# SW6208_A_A_B_C_L_188.net
KiCad netlist of a schematic drawn in Altium Designer
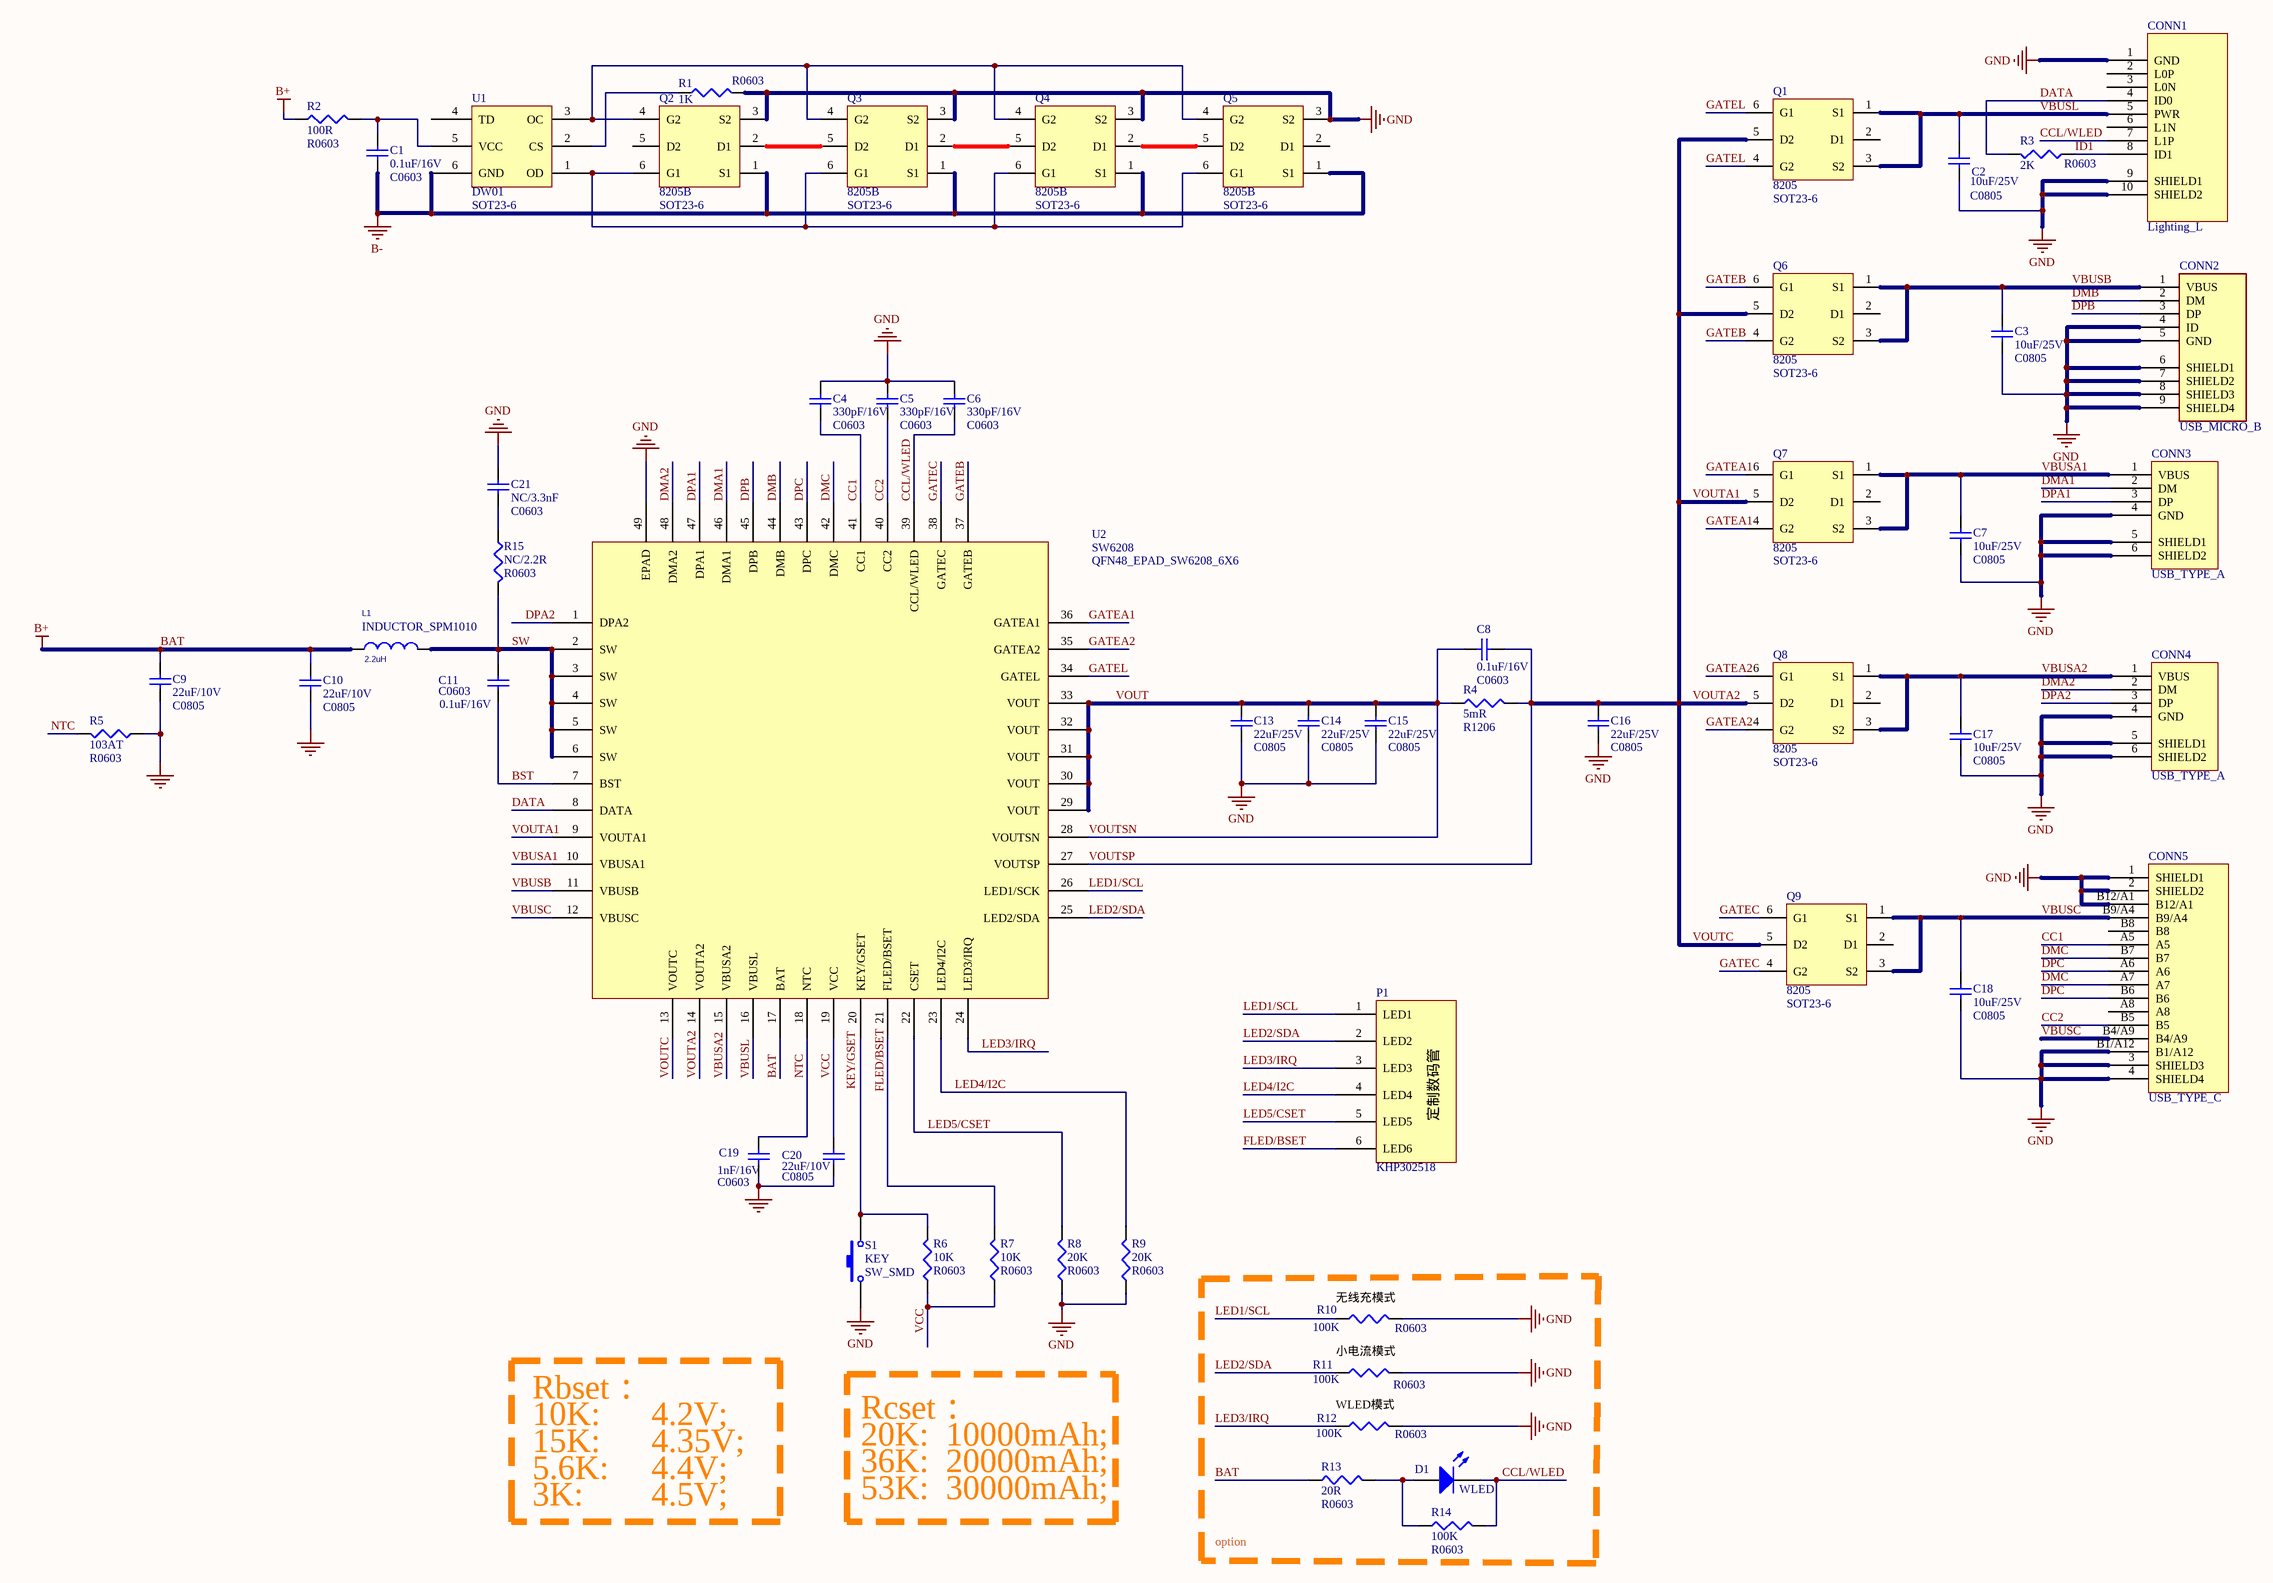
[diagram p0: SW6208+A+A+B+C+L+快充188数码管.SchDoc]

(export (version "E")
  (design (tool "Eeschema 10.0.6"))
  (components
    (comp (ref "C1")
      (value "0.1uF/16V")
      (footprint "C0603")
      (description "Capacitor")
      (fields (field (name "PUBLISHER") "Altium Limited"))
      (libsource (lib "参考设计器件原理图更新") (part "CAP0603"))
    )
    (comp (ref "C2")
      (value "10uF/25V")
      (footprint "C0805")
      (description "Capacitor")
      (fields (field (name "PUBLISHER") "Altium Limited"))
      (libsource (lib "参考设计器件原理图更新") (part "CAP0805"))
    )
    (comp (ref "C3")
      (value "10uF/25V")
      (footprint "C0805")
      (description "Capacitor")
      (fields (field (name "PUBLISHER") "Altium Limited"))
      (libsource (lib "参考设计器件原理图更新") (part "CAP0805"))
    )
    (comp (ref "C4")
      (value "330pF/16V")
      (footprint "C0603")
      (description "Capacitor")
      (fields (field (name "PUBLISHER") "Altium Limited"))
      (libsource (lib "参考设计器件原理图更新") (part "CAP0603"))
    )
    (comp (ref "C5")
      (value "330pF/16V")
      (footprint "C0603")
      (description "Capacitor")
      (fields (field (name "PUBLISHER") "Altium Limited"))
      (libsource (lib "参考设计器件原理图更新") (part "CAP0603"))
    )
    (comp (ref "C6")
      (value "330pF/16V")
      (footprint "C0603")
      (description "Capacitor")
      (fields (field (name "PUBLISHER") "Altium Limited"))
      (libsource (lib "参考设计器件原理图更新") (part "CAP0603"))
    )
    (comp (ref "C7")
      (value "10uF/25V")
      (footprint "C0805")
      (description "Capacitor")
      (fields (field (name "PUBLISHER") "Altium Limited"))
      (libsource (lib "参考设计器件原理图更新") (part "CAP0805"))
    )
    (comp (ref "C8")
      (value "0.1uF/16V")
      (footprint "C0603")
      (description "Capacitor")
      (fields (field (name "PUBLISHER") "Altium Limited"))
      (libsource (lib "参考设计器件原理图更新") (part "CAP0603"))
    )
    (comp (ref "C9")
      (value "22uF/10V")
      (footprint "C0805")
      (description "Capacitor")
      (fields (field (name "PUBLISHER") "Altium Limited"))
      (libsource (lib "参考设计器件原理图更新") (part "CAP0805"))
    )
    (comp (ref "C10")
      (value "22uF/10V")
      (footprint "C0805")
      (description "Capacitor")
      (fields (field (name "PUBLISHER") "Altium Limited"))
      (libsource (lib "参考设计器件原理图更新") (part "CAP0805"))
    )
    (comp (ref "C11")
      (value "0.1uF/16V")
      (footprint "C0603")
      (description "Capacitor")
      (fields (field (name "PUBLISHER") "Altium Limited"))
      (libsource (lib "参考设计器件原理图更新") (part "CAP0603"))
    )
    (comp (ref "C13")
      (value "22uF/25V")
      (footprint "C0805")
      (description "Capacitor")
      (fields (field (name "PUBLISHER") "Altium Limited"))
      (libsource (lib "参考设计器件原理图更新") (part "CAP0805"))
    )
    (comp (ref "C14")
      (value "22uF/25V")
      (footprint "C0805")
      (description "Capacitor")
      (fields (field (name "PUBLISHER") "Altium Limited"))
      (libsource (lib "参考设计器件原理图更新") (part "CAP0805"))
    )
    (comp (ref "C15")
      (value "22uF/25V")
      (footprint "C0805")
      (description "Capacitor")
      (fields (field (name "PUBLISHER") "Altium Limited"))
      (libsource (lib "参考设计器件原理图更新") (part "CAP0805"))
    )
    (comp (ref "C16")
      (value "22uF/25V")
      (footprint "C0805")
      (description "Capacitor")
      (fields (field (name "PUBLISHER") "Altium Limited"))
      (libsource (lib "参考设计器件原理图更新") (part "CAP0805"))
    )
    (comp (ref "C17")
      (value "10uF/25V")
      (footprint "C0805")
      (description "Capacitor")
      (fields (field (name "PUBLISHER") "Altium Limited"))
      (libsource (lib "参考设计器件原理图更新") (part "CAP0805"))
    )
    (comp (ref "C18")
      (value "10uF/25V")
      (footprint "C0805")
      (description "Capacitor")
      (fields (field (name "PUBLISHER") "Altium Limited"))
      (libsource (lib "参考设计器件原理图更新") (part "CAP0805"))
    )
    (comp (ref "C19")
      (value "1nF/16V")
      (footprint "C0603")
      (description "Capacitor")
      (fields (field (name "PUBLISHER") "Altium Limited"))
      (libsource (lib "参考设计器件原理图更新") (part "CAP0603"))
    )
    (comp (ref "C20")
      (value "22uF/10V")
      (footprint "C0805")
      (description "Capacitor")
      (fields (field (name "PUBLISHER") "Altium Limited"))
      (libsource (lib "参考设计器件原理图更新") (part "CAP0805"))
    )
    (comp (ref "C21")
      (value "NC/3.3nF")
      (footprint "C0603")
      (description "Capacitor")
      (fields (field (name "PUBLISHER") "Altium Limited"))
      (libsource (lib "参考设计器件原理图更新") (part "CAP0603"))
    )
    (comp (ref "CONN1")
      (value "Lighting_L")
      (footprint "Lighting")
      (libsource (lib "参考设计器件原理图更新") (part "LIGHTING_PORT"))
    )
    (comp (ref "CONN2")
      (value "USB_MICRO_B")
      (footprint "USB_MICRO_B")
      (libsource (lib "参考设计器件原理图更新") (part "USB_MICRO_B"))
    )
    (comp (ref "CONN3")
      (value "USB_TYPE_A")
      (footprint "USB_TYPE_A")
      (libsource (lib "参考设计器件原理图更新") (part "USB_TYPE_A"))
    )
    (comp (ref "CONN4")
      (value "USB_TYPE_A")
      (footprint "USB_TYPE_A")
      (libsource (lib "参考设计器件原理图更新") (part "USB_TYPE_A"))
    )
    (comp (ref "CONN5")
      (value "USB_TYPE_C")
      (footprint "LOUISAD:USB_TYPE_C")
      (libsource (lib "参考设计器件原理图更新") (part "USB_TYPE_C"))
    )
    (comp (ref "D1")
      (value "WLED")
      (footprint "LED_5MM")
      (fields (field (name "PUBLISHER") "Altium Limited"))
      (libsource (lib "参考设计器件原理图更新") (part "WLED"))
    )
    (comp (ref "L1")
      (value "2.2uH")
      (footprint "INDUCTOR_SPM1010")
      (description "INDUCTOR")
      (libsource (lib "参考设计器件原理图更新") (part "INDUCTOR_SPM1010"))
    )
    (comp (ref "P1")
      (value "KHP302518")
      (footprint "KHP-SEG-6")
      (libsource (lib "参考设计器件原理图更新") (part "KHP302518"))
    )
    (comp (ref "Q1")
      (value "8205")
      (footprint "SOT23-6")
      (description "NMOS")
      (fields (field (name "FOOTPRINF") "SOT23-6"))
      (libsource (lib "参考设计器件原理图更新") (part "8205"))
    )
    (comp (ref "Q2")
      (value "8205B")
      (footprint "SOT23-6")
      (description "NMOS")
      (fields (field (name "FOOTPRINF") "SOT23-6"))
      (libsource (lib "") (part "8205_1"))
    )
    (comp (ref "Q3")
      (value "8205B")
      (footprint "SOT23-6")
      (description "NMOS")
      (fields (field (name "FOOTPRINF") "SOT23-6"))
      (libsource (lib "") (part "8205_1"))
    )
    (comp (ref "Q4")
      (value "8205B")
      (footprint "SOT23-6")
      (description "NMOS")
      (fields (field (name "FOOTPRINF") "SOT23-6"))
      (libsource (lib "") (part "8205_1"))
    )
    (comp (ref "Q5")
      (value "8205B")
      (footprint "SOT23-6")
      (description "NMOS")
      (fields (field (name "FOOTPRINF") "SOT23-6"))
      (libsource (lib "") (part "8205_1"))
    )
    (comp (ref "Q6")
      (value "8205")
      (footprint "SOT23-6")
      (description "NMOS")
      (fields (field (name "FOOTPRINF") "SOT23-6"))
      (libsource (lib "参考设计器件原理图更新") (part "8205"))
    )
    (comp (ref "Q7")
      (value "8205")
      (footprint "SOT23-6")
      (description "NMOS")
      (fields (field (name "FOOTPRINF") "SOT23-6"))
      (libsource (lib "参考设计器件原理图更新") (part "8205"))
    )
    (comp (ref "Q8")
      (value "8205")
      (footprint "SOT23-6")
      (description "NMOS")
      (fields (field (name "FOOTPRINF") "SOT23-6"))
      (libsource (lib "参考设计器件原理图更新") (part "8205"))
    )
    (comp (ref "Q9")
      (value "8205")
      (footprint "SOT23-6")
      (description "NMOS")
      (fields (field (name "FOOTPRINF") "SOT23-6"))
      (libsource (lib "参考设计器件原理图更新") (part "8205"))
    )
    (comp (ref "R1")
      (value "1K")
      (footprint "R0603")
      (description "Resistor")
      (fields (field (name "PUBLISHER") "Altium Limited"))
      (libsource (lib "参考设计器件原理图更新") (part "RES_0603"))
    )
    (comp (ref "R2")
      (value "100R")
      (footprint "R0603")
      (description "Resistor")
      (fields (field (name "PUBLISHER") "Altium Limited"))
      (libsource (lib "参考设计器件原理图更新") (part "RES_0603"))
    )
    (comp (ref "R3")
      (value "2K")
      (footprint "R0603")
      (description "Resistor")
      (fields (field (name "PUBLISHER") "Altium Limited"))
      (libsource (lib "参考设计器件原理图更新") (part "RES_0603"))
    )
    (comp (ref "R4")
      (value "5mR")
      (footprint "R1206")
      (description "Resistor")
      (fields (field (name "PUBLISHER") "Altium Limited"))
      (libsource (lib "参考设计器件原理图更新") (part "RES_1206"))
    )
    (comp (ref "R5")
      (value "103AT")
      (footprint "R0603")
      (description "Resistor")
      (fields (field (name "PUBLISHER") "Altium Limited"))
      (libsource (lib "参考设计器件原理图更新") (part "RES_0603"))
    )
    (comp (ref "R6")
      (value "10K")
      (footprint "R0603")
      (description "Resistor")
      (fields (field (name "PUBLISHER") "Altium Limited"))
      (libsource (lib "参考设计器件原理图更新") (part "RES_0603"))
    )
    (comp (ref "R7")
      (value "10K")
      (footprint "R0603")
      (description "Resistor")
      (fields (field (name "PUBLISHER") "Altium Limited"))
      (libsource (lib "参考设计器件原理图更新") (part "RES_0603"))
    )
    (comp (ref "R8")
      (value "20K")
      (footprint "R0603")
      (description "Resistor")
      (fields (field (name "PUBLISHER") "Altium Limited"))
      (libsource (lib "参考设计器件原理图更新") (part "RES_0603"))
    )
    (comp (ref "R9")
      (value "20K")
      (footprint "R0603")
      (description "Resistor")
      (fields (field (name "PUBLISHER") "Altium Limited"))
      (libsource (lib "参考设计器件原理图更新") (part "RES_0603"))
    )
    (comp (ref "R10")
      (value "100K")
      (footprint "R0603")
      (description "Resistor")
      (fields (field (name "PUBLISHER") "Altium Limited"))
      (libsource (lib "参考设计器件原理图更新") (part "RES_0603"))
    )
    (comp (ref "R11")
      (value "100K")
      (footprint "R0603")
      (description "Resistor")
      (fields (field (name "PUBLISHER") "Altium Limited"))
      (libsource (lib "参考设计器件原理图更新") (part "RES_0603"))
    )
    (comp (ref "R12")
      (value "100K")
      (footprint "R0603")
      (description "Resistor")
      (fields (field (name "PUBLISHER") "Altium Limited"))
      (libsource (lib "参考设计器件原理图更新") (part "RES_0603"))
    )
    (comp (ref "R13")
      (value "20R")
      (footprint "R0603")
      (description "Resistor")
      (fields (field (name "PUBLISHER") "Altium Limited"))
      (libsource (lib "参考设计器件原理图更新") (part "RES_0603"))
    )
    (comp (ref "R14")
      (value "100K")
      (footprint "R0603")
      (description "Resistor")
      (fields (field (name "PUBLISHER") "Altium Limited"))
      (libsource (lib "参考设计器件原理图更新") (part "RES_0603"))
    )
    (comp (ref "R15")
      (value "NC/2.2R")
      (footprint "R0603")
      (description "Resistor")
      (fields (field (name "PUBLISHER") "Altium Limited"))
      (libsource (lib "参考设计器件原理图更新") (part "RES_0603"))
    )
    (comp (ref "S1")
      (value "KEY")
      (footprint "SW_SMD")
      (fields (field (name "FOOTPRINF") "SW_SMD"))
      (libsource (lib "参考设计器件原理图更新") (part "SW K"))
    )
    (comp (ref "U1")
      (value "DW01")
      (footprint "SOT23-6")
      (description "BAT_PROTECT_IC")
      (libsource (lib "参考设计器件原理图更新") (part "DW01"))
    )
    (comp (ref "U2")
      (value "SW6208")
      (footprint "QFN48_EPAD_SW6208_6X6")
      (description "IC")
      (libsource (lib "芯片型号原理图") (part "SW6208"))
    )
  )
  (nets
    (net (code "1") (name "/BST") (class "Default")
      (node (ref "C11") (pin "1") (pinfunction "1_1") (pintype "passive"))
      (node (ref "U2") (pin "7") (pinfunction "BST_7") (pintype "passive"))
    )
    (net (code "2") (name "/CC1") (class "Default")
      (node (ref "C4") (pin "1") (pinfunction "1_1") (pintype "passive"))
      (node (ref "CONN5") (pin "A5") (pinfunction "A5_A5") (pintype "passive"))
      (node (ref "U2") (pin "41") (pinfunction "CC1_41") (pintype "passive"))
    )
    (net (code "3") (name "/CC2") (class "Default")
      (node (ref "C5") (pin "1") (pinfunction "1_1") (pintype "passive"))
      (node (ref "CONN5") (pin "B5") (pinfunction "B5_B5") (pintype "passive"))
      (node (ref "U2") (pin "40") (pinfunction "CC2_40") (pintype "passive"))
    )
    (net (code "4") (name "/CCL{slash}WLED") (class "Default")
      (node (ref "C6") (pin "1") (pinfunction "1_1") (pintype "passive"))
      (node (ref "CONN1") (pin "7") (pinfunction "L1P_7") (pintype "passive"))
      (node (ref "D1") (pin "2") (pinfunction "K_2") (pintype "passive"))
      (node (ref "R14") (pin "2") (pinfunction "2_2") (pintype "passive"))
      (node (ref "U2") (pin "39") (pinfunction "CCL/WLED_39") (pintype "passive"))
    )
    (net (code "5") (name "/DATA") (class "Default")
      (node (ref "CONN1") (pin "4") (pinfunction "ID0_4") (pintype "passive"))
      (node (ref "R3") (pin "2") (pinfunction "2_2") (pintype "passive"))
      (node (ref "U2") (pin "8") (pinfunction "DATA_8") (pintype "passive"))
    )
    (net (code "6") (name "/DMA1") (class "Default")
      (node (ref "CONN3") (pin "2") (pinfunction "DM_2") (pintype "passive"))
      (node (ref "U2") (pin "46") (pinfunction "DMA1_46") (pintype "passive"))
    )
    (net (code "7") (name "/DMA2") (class "Default")
      (node (ref "CONN4") (pin "2") (pinfunction "DM_2") (pintype "passive"))
      (node (ref "U2") (pin "48") (pinfunction "DMA2_48") (pintype "passive"))
    )
    (net (code "8") (name "/DMB") (class "Default")
      (node (ref "CONN2") (pin "2") (pinfunction "DM_2") (pintype "passive"))
      (node (ref "U2") (pin "44") (pinfunction "DMB_44") (pintype "passive"))
    )
    (net (code "9") (name "/DMC") (class "Default")
      (node (ref "CONN5") (pin "A7") (pinfunction "A7_A7") (pintype "passive"))
      (node (ref "CONN5") (pin "B7") (pinfunction "B7_B7") (pintype "passive"))
      (node (ref "U2") (pin "42") (pinfunction "DMC_42") (pintype "passive"))
    )
    (net (code "10") (name "/DPA1") (class "Default")
      (node (ref "CONN3") (pin "3") (pinfunction "DP_3") (pintype "passive"))
      (node (ref "U2") (pin "47") (pinfunction "DPA1_47") (pintype "passive"))
    )
    (net (code "11") (name "/DPA2") (class "Default")
      (node (ref "CONN4") (pin "3") (pinfunction "DP_3") (pintype "passive"))
      (node (ref "U2") (pin "1") (pinfunction "DPA2_1") (pintype "passive"))
    )
    (net (code "12") (name "/DPB") (class "Default")
      (node (ref "CONN2") (pin "3") (pinfunction "DP_3") (pintype "passive"))
      (node (ref "U2") (pin "45") (pinfunction "DPB_45") (pintype "passive"))
    )
    (net (code "13") (name "/DPC") (class "Default")
      (node (ref "CONN5") (pin "A6") (pinfunction "A6_A6") (pintype "passive"))
      (node (ref "CONN5") (pin "B6") (pinfunction "B6_B6") (pintype "passive"))
      (node (ref "U2") (pin "43") (pinfunction "DPC_43") (pintype "passive"))
    )
    (net (code "14") (name "/FLED{slash}BSET") (class "Default")
      (node (ref "P1") (pin "6") (pinfunction "LED6_6") (pintype "passive"))
      (node (ref "R7") (pin "2") (pinfunction "2_2") (pintype "passive"))
      (node (ref "U2") (pin "21") (pinfunction "FLED/BSET_21") (pintype "passive"))
    )
    (net (code "15") (name "/GATEA1") (class "Default")
      (node (ref "Q7") (pin "4") (pinfunction "G2_4") (pintype "passive"))
      (node (ref "Q7") (pin "6") (pinfunction "G1_6") (pintype "passive"))
      (node (ref "U2") (pin "36") (pinfunction "GATEA1_36") (pintype "passive"))
    )
    (net (code "16") (name "/GATEA2") (class "Default")
      (node (ref "Q8") (pin "4") (pinfunction "G2_4") (pintype "passive"))
      (node (ref "Q8") (pin "6") (pinfunction "G1_6") (pintype "passive"))
      (node (ref "U2") (pin "35") (pinfunction "GATEA2_35") (pintype "passive"))
    )
    (net (code "17") (name "/GATEB") (class "Default")
      (node (ref "Q6") (pin "4") (pinfunction "G2_4") (pintype "passive"))
      (node (ref "Q6") (pin "6") (pinfunction "G1_6") (pintype "passive"))
      (node (ref "U2") (pin "37") (pinfunction "GATEB_37") (pintype "passive"))
    )
    (net (code "18") (name "/GATEC") (class "Default")
      (node (ref "Q9") (pin "4") (pinfunction "G2_4") (pintype "passive"))
      (node (ref "Q9") (pin "6") (pinfunction "G1_6") (pintype "passive"))
      (node (ref "U2") (pin "38") (pinfunction "GATEC_38") (pintype "passive"))
    )
    (net (code "19") (name "/GATEL") (class "Default")
      (node (ref "Q1") (pin "4") (pinfunction "G2_4") (pintype "passive"))
      (node (ref "Q1") (pin "6") (pinfunction "G1_6") (pintype "passive"))
      (node (ref "U2") (pin "34") (pinfunction "GATEL_34") (pintype "passive"))
    )
    (net (code "20") (name "/ID1") (class "Default")
      (node (ref "CONN1") (pin "8") (pinfunction "ID1_8") (pintype "passive"))
      (node (ref "R3") (pin "1") (pinfunction "1_1") (pintype "passive"))
    )
    (net (code "22") (name "/LED1{slash}SCL") (class "Default")
      (node (ref "P1") (pin "1") (pinfunction "LED1_1") (pintype "passive"))
      (node (ref "R10") (pin "1") (pinfunction "1_1") (pintype "passive"))
      (node (ref "U2") (pin "26") (pinfunction "LED1/SCK_26") (pintype "passive"))
    )
    (net (code "23") (name "/LED2{slash}SDA") (class "Default")
      (node (ref "P1") (pin "2") (pinfunction "LED2_2") (pintype "passive"))
      (node (ref "R11") (pin "1") (pinfunction "1_1") (pintype "passive"))
      (node (ref "U2") (pin "25") (pinfunction "LED2/SDA_25") (pintype "passive"))
    )
    (net (code "24") (name "/LED3{slash}IRQ") (class "Default")
      (node (ref "P1") (pin "3") (pinfunction "LED3_3") (pintype "passive"))
      (node (ref "R12") (pin "1") (pinfunction "1_1") (pintype "passive"))
      (node (ref "U2") (pin "24") (pinfunction "LED3/IRQ_24") (pintype "passive"))
    )
    (net (code "25") (name "/LED4{slash}I2C") (class "Default")
      (node (ref "P1") (pin "4") (pinfunction "LED4_4") (pintype "passive"))
      (node (ref "R9") (pin "2") (pinfunction "2_2") (pintype "passive"))
      (node (ref "U2") (pin "23") (pinfunction "LED4/I2C_23") (pintype "passive"))
    )
    (net (code "26") (name "/LED5{slash}CSET") (class "Default")
      (node (ref "P1") (pin "5") (pinfunction "LED5_5") (pintype "passive"))
      (node (ref "R8") (pin "2") (pinfunction "2_2") (pintype "passive"))
      (node (ref "U2") (pin "22") (pinfunction "CSET_22") (pintype "passive"))
    )
    (net (code "27") (name "/NTC") (class "Default")
      (node (ref "C19") (pin "1") (pinfunction "1_1") (pintype "passive"))
      (node (ref "R5") (pin "2") (pinfunction "2_2") (pintype "passive"))
      (node (ref "U2") (pin "18") (pinfunction "NTC_18") (pintype "passive"))
    )
    (net (code "28") (name "/SW") (class "Default")
      (node (ref "C11") (pin "2") (pinfunction "2_2") (pintype "passive"))
      (node (ref "L1") (pin "2") (pinfunction "2_2") (pintype "passive"))
      (node (ref "R15") (pin "2") (pinfunction "2_2") (pintype "passive"))
      (node (ref "U2") (pin "2") (pinfunction "SW_2") (pintype "passive"))
      (node (ref "U2") (pin "3") (pinfunction "SW_3") (pintype "passive"))
      (node (ref "U2") (pin "4") (pinfunction "SW_4") (pintype "passive"))
      (node (ref "U2") (pin "5") (pinfunction "SW_5") (pintype "passive"))
      (node (ref "U2") (pin "6") (pinfunction "SW_6") (pintype "passive"))
    )
    (net (code "29") (name "/VBUSA1") (class "Default")
      (node (ref "C7") (pin "2") (pinfunction "2_2") (pintype "passive"))
      (node (ref "CONN3") (pin "1") (pinfunction "VBUS_1") (pintype "passive"))
      (node (ref "Q7") (pin "1") (pinfunction "S1_1") (pintype "passive"))
      (node (ref "Q7") (pin "3") (pinfunction "S2_3") (pintype "passive"))
      (node (ref "U2") (pin "10") (pinfunction "VBUSA1_10") (pintype "passive"))
    )
    (net (code "30") (name "/VBUSA2") (class "Default")
      (node (ref "C17") (pin "2") (pinfunction "2_2") (pintype "passive"))
      (node (ref "CONN4") (pin "1") (pinfunction "VBUS_1") (pintype "passive"))
      (node (ref "Q8") (pin "1") (pinfunction "S1_1") (pintype "passive"))
      (node (ref "Q8") (pin "3") (pinfunction "S2_3") (pintype "passive"))
      (node (ref "U2") (pin "15") (pinfunction "VBUSA2_15") (pintype "passive"))
    )
    (net (code "31") (name "/VBUSB") (class "Default")
      (node (ref "C3") (pin "2") (pinfunction "2_2") (pintype "passive"))
      (node (ref "CONN2") (pin "1") (pinfunction "VBUS_1") (pintype "passive"))
      (node (ref "Q6") (pin "1") (pinfunction "S1_1") (pintype "passive"))
      (node (ref "Q6") (pin "3") (pinfunction "S2_3") (pintype "passive"))
      (node (ref "U2") (pin "11") (pinfunction "VBUSB_11") (pintype "passive"))
    )
    (net (code "32") (name "/VBUSC") (class "Default")
      (node (ref "C18") (pin "2") (pinfunction "2_2") (pintype "passive"))
      (node (ref "CONN5") (pin "B4/A9") (pinfunction "B4/A9_B4/A9") (pintype "passive"))
      (node (ref "CONN5") (pin "B9/A4") (pinfunction "B9/A4_B9/A4") (pintype "passive"))
      (node (ref "Q9") (pin "1") (pinfunction "S1_1") (pintype "passive"))
      (node (ref "Q9") (pin "3") (pinfunction "S2_3") (pintype "passive"))
      (node (ref "U2") (pin "12") (pinfunction "VBUSC_12") (pintype "passive"))
    )
    (net (code "33") (name "/VBUSL") (class "Default")
      (node (ref "C2") (pin "2") (pinfunction "2_2") (pintype "passive"))
      (node (ref "CONN1") (pin "5") (pinfunction "PWR_5") (pintype "passive"))
      (node (ref "Q1") (pin "1") (pinfunction "S1_1") (pintype "passive"))
      (node (ref "Q1") (pin "3") (pinfunction "S2_3") (pintype "passive"))
      (node (ref "U2") (pin "16") (pinfunction "VBUSL_16") (pintype "passive"))
    )
    (net (code "34") (name "/VCC") (class "Default")
      (node (ref "C20") (pin "1") (pinfunction "1_1") (pintype "passive"))
      (node (ref "R6") (pin "1") (pinfunction "1_1") (pintype "passive"))
      (node (ref "R7") (pin "1") (pinfunction "1_1") (pintype "passive"))
      (node (ref "U2") (pin "19") (pinfunction "VCC_19") (pintype "passive"))
    )
    (net (code "35") (name "/VOUT") (class "Default")
      (node (ref "C13") (pin "2") (pinfunction "2_2") (pintype "passive"))
      (node (ref "C14") (pin "2") (pinfunction "2_2") (pintype "passive"))
      (node (ref "C15") (pin "2") (pinfunction "2_2") (pintype "passive"))
      (node (ref "C8") (pin "1") (pinfunction "1_1") (pintype "passive"))
      (node (ref "R4") (pin "1") (pinfunction "1_1") (pintype "passive"))
      (node (ref "U2") (pin "28") (pinfunction "VOUTSN_28") (pintype "passive"))
      (node (ref "U2") (pin "29") (pinfunction "VOUT_29") (pintype "passive"))
      (node (ref "U2") (pin "30") (pinfunction "VOUT_30") (pintype "passive"))
      (node (ref "U2") (pin "31") (pinfunction "VOUT_31") (pintype "passive"))
      (node (ref "U2") (pin "32") (pinfunction "VOUT_32") (pintype "passive"))
      (node (ref "U2") (pin "33") (pinfunction "VOUT_33") (pintype "passive"))
    )
    (net (code "36") (name "/VOUTA1") (class "Default")
      (node (ref "C16") (pin "2") (pinfunction "2_2") (pintype "passive"))
      (node (ref "C8") (pin "2") (pinfunction "2_2") (pintype "passive"))
      (node (ref "Q1") (pin "5") (pinfunction "D2_5") (pintype "passive"))
      (node (ref "Q6") (pin "5") (pinfunction "D2_5") (pintype "passive"))
      (node (ref "Q7") (pin "5") (pinfunction "D2_5") (pintype "passive"))
      (node (ref "Q8") (pin "5") (pinfunction "D2_5") (pintype "passive"))
      (node (ref "Q9") (pin "5") (pinfunction "D2_5") (pintype "passive"))
      (node (ref "R4") (pin "2") (pinfunction "2_2") (pintype "passive"))
      (node (ref "U2") (pin "13") (pinfunction "VOUTC_13") (pintype "passive"))
      (node (ref "U2") (pin "14") (pinfunction "VOUTA2_14") (pintype "passive"))
      (node (ref "U2") (pin "27") (pinfunction "VOUTSP_27") (pintype "passive"))
      (node (ref "U2") (pin "9") (pinfunction "VOUTA1_9") (pintype "passive"))
    )
    (net (code "37") (name "B+") (class "Default")
      (node (ref "C10") (pin "2") (pinfunction "2_2") (pintype "passive"))
      (node (ref "C9") (pin "2") (pinfunction "2_2") (pintype "passive"))
      (node (ref "L1") (pin "1") (pinfunction "1_1") (pintype "passive"))
      (node (ref "R13") (pin "1") (pinfunction "1_1") (pintype "passive"))
      (node (ref "R2") (pin "1") (pinfunction "1_1") (pintype "passive"))
      (node (ref "U2") (pin "17") (pinfunction "BAT_17") (pintype "passive"))
    )
    (net (code "38") (name "B-") (class "Default")
      (node (ref "C1") (pin "1") (pinfunction "1_1") (pintype "passive"))
      (node (ref "Q2") (pin "1") (pinfunction "S1_1") (pintype "passive"))
      (node (ref "Q3") (pin "1") (pinfunction "S1_1") (pintype "passive"))
      (node (ref "Q4") (pin "1") (pinfunction "S1_1") (pintype "passive"))
      (node (ref "Q5") (pin "1") (pinfunction "S1_1") (pintype "passive"))
      (node (ref "U1") (pin "6") (pinfunction "GND_6") (pintype "passive"))
    )
    (net (code "39") (name "GND") (class "Default")
      (node (ref "C10") (pin "1") (pinfunction "1_1") (pintype "passive"))
      (node (ref "C13") (pin "1") (pinfunction "1_1") (pintype "passive"))
      (node (ref "C14") (pin "1") (pinfunction "1_1") (pintype "passive"))
      (node (ref "C15") (pin "1") (pinfunction "1_1") (pintype "passive"))
      (node (ref "C16") (pin "1") (pinfunction "1_1") (pintype "passive"))
      (node (ref "C17") (pin "1") (pinfunction "1_1") (pintype "passive"))
      (node (ref "C18") (pin "1") (pinfunction "1_1") (pintype "passive"))
      (node (ref "C19") (pin "2") (pinfunction "2_2") (pintype "passive"))
      (node (ref "C2") (pin "1") (pinfunction "1_1") (pintype "passive"))
      (node (ref "C20") (pin "2") (pinfunction "2_2") (pintype "passive"))
      (node (ref "C21") (pin "2") (pinfunction "2_2") (pintype "passive"))
      (node (ref "C3") (pin "1") (pinfunction "1_1") (pintype "passive"))
      (node (ref "C4") (pin "2") (pinfunction "2_2") (pintype "passive"))
      (node (ref "C5") (pin "2") (pinfunction "2_2") (pintype "passive"))
      (node (ref "C6") (pin "2") (pinfunction "2_2") (pintype "passive"))
      (node (ref "C7") (pin "1") (pinfunction "1_1") (pintype "passive"))
      (node (ref "C9") (pin "1") (pinfunction "1_1") (pintype "passive"))
      (node (ref "CONN1") (pin "1") (pinfunction "GND_1") (pintype "passive"))
      (node (ref "CONN1") (pin "10") (pinfunction "SHIELD2_10") (pintype "passive"))
      (node (ref "CONN1") (pin "9") (pinfunction "SHIELD1_9") (pintype "passive"))
      (node (ref "CONN2") (pin "4") (pinfunction "ID_4") (pintype "passive"))
      (node (ref "CONN2") (pin "5") (pinfunction "GND_5") (pintype "passive"))
      (node (ref "CONN2") (pin "6") (pinfunction "SHIELD1_6") (pintype "passive"))
      (node (ref "CONN2") (pin "7") (pinfunction "SHIELD2_7") (pintype "passive"))
      (node (ref "CONN2") (pin "8") (pinfunction "SHIELD3_8") (pintype "passive"))
      (node (ref "CONN2") (pin "9") (pinfunction "SHIELD4_9") (pintype "passive"))
      (node (ref "CONN3") (pin "4") (pinfunction "GND_4") (pintype "passive"))
      (node (ref "CONN3") (pin "5") (pinfunction "SHIELD1_5") (pintype "passive"))
      (node (ref "CONN3") (pin "6") (pinfunction "SHIELD2_6") (pintype "passive"))
      (node (ref "CONN4") (pin "4") (pinfunction "GND_4") (pintype "passive"))
      (node (ref "CONN4") (pin "5") (pinfunction "SHIELD1_5") (pintype "passive"))
      (node (ref "CONN4") (pin "6") (pinfunction "SHIELD2_6") (pintype "passive"))
      (node (ref "CONN5") (pin "1") (pinfunction "SHIELD1_1") (pintype "passive"))
      (node (ref "CONN5") (pin "2") (pinfunction "SHIELD2_2") (pintype "passive"))
      (node (ref "CONN5") (pin "3") (pinfunction "SHIELD3_3") (pintype "passive"))
      (node (ref "CONN5") (pin "4") (pinfunction "SHIELD4_4") (pintype "passive"))
      (node (ref "CONN5") (pin "B1/A12") (pinfunction "B1/A12_B1/A12") (pintype "passive"))
      (node (ref "CONN5") (pin "B12/A1") (pinfunction "B12/A1_B12/A1") (pintype "passive"))
      (node (ref "Q2") (pin "3") (pinfunction "S2_3") (pintype "passive"))
      (node (ref "Q3") (pin "3") (pinfunction "S2_3") (pintype "passive"))
      (node (ref "Q4") (pin "3") (pinfunction "S2_3") (pintype "passive"))
      (node (ref "Q5") (pin "3") (pinfunction "S2_3") (pintype "passive"))
      (node (ref "R1") (pin "2") (pinfunction "2_2") (pintype "passive"))
      (node (ref "R10") (pin "2") (pinfunction "2_2") (pintype "passive"))
      (node (ref "R11") (pin "2") (pinfunction "2_2") (pintype "passive"))
      (node (ref "R12") (pin "2") (pinfunction "2_2") (pintype "passive"))
      (node (ref "R5") (pin "1") (pinfunction "1_1") (pintype "passive"))
      (node (ref "R8") (pin "1") (pinfunction "1_1") (pintype "passive"))
      (node (ref "R9") (pin "1") (pinfunction "1_1") (pintype "passive"))
      (node (ref "S1") (pin "1") (pinfunction "1_1") (pintype "passive"))
      (node (ref "U2") (pin "49") (pinfunction "EPAD_49") (pintype "passive"))
    )
    (net (code "40") (name "Net-(C21-Pad1)") (class "Default")
      (node (ref "C21") (pin "1") (pinfunction "1_1") (pintype "passive"))
      (node (ref "R15") (pin "1") (pinfunction "1_1") (pintype "passive"))
    )
    (net (code "41") (name "Net-(D1-A)") (class "Default")
      (node (ref "D1") (pin "1") (pinfunction "A_1") (pintype "passive"))
      (node (ref "R13") (pin "2") (pinfunction "2_2") (pintype "passive"))
      (node (ref "R14") (pin "1") (pinfunction "1_1") (pintype "passive"))
    )
    (net (code "42") (name "Net-(Q2-D1)") (class "Default")
      (node (ref "Q2") (pin "2") (pinfunction "D1_2") (pintype "passive"))
      (node (ref "Q3") (pin "5") (pinfunction "D2_5") (pintype "passive"))
    )
    (net (code "43") (name "Net-(Q2-G1)") (class "Default")
      (node (ref "Q2") (pin "6") (pinfunction "G1_6") (pintype "passive"))
      (node (ref "Q3") (pin "6") (pinfunction "G1_6") (pintype "passive"))
      (node (ref "Q4") (pin "6") (pinfunction "G1_6") (pintype "passive"))
      (node (ref "Q5") (pin "6") (pinfunction "G1_6") (pintype "passive"))
      (node (ref "U1") (pin "1") (pinfunction "OD_1") (pintype "passive"))
    )
    (net (code "44") (name "Net-(Q2-G2)") (class "Default")
      (node (ref "Q2") (pin "4") (pinfunction "G2_4") (pintype "passive"))
      (node (ref "Q3") (pin "4") (pinfunction "G2_4") (pintype "passive"))
      (node (ref "Q4") (pin "4") (pinfunction "G2_4") (pintype "passive"))
      (node (ref "Q5") (pin "4") (pinfunction "G2_4") (pintype "passive"))
      (node (ref "U1") (pin "3") (pinfunction "OC_3") (pintype "passive"))
    )
    (net (code "45") (name "Net-(Q3-D1)") (class "Default")
      (node (ref "Q3") (pin "2") (pinfunction "D1_2") (pintype "passive"))
      (node (ref "Q4") (pin "5") (pinfunction "D2_5") (pintype "passive"))
    )
    (net (code "46") (name "Net-(Q4-D1)") (class "Default")
      (node (ref "Q4") (pin "2") (pinfunction "D1_2") (pintype "passive"))
      (node (ref "Q5") (pin "5") (pinfunction "D2_5") (pintype "passive"))
    )
    (net (code "47") (name "Net-(U1-CS)") (class "Default")
      (node (ref "R1") (pin "1") (pinfunction "1_1") (pintype "passive"))
      (node (ref "U1") (pin "2") (pinfunction "CS_2") (pintype "passive"))
    )
    (net (code "48") (name "Net-(U1-VCC)") (class "Default")
      (node (ref "C1") (pin "2") (pinfunction "2_2") (pintype "passive"))
      (node (ref "R2") (pin "2") (pinfunction "2_2") (pintype "passive"))
      (node (ref "U1") (pin "5") (pinfunction "VCC_5") (pintype "passive"))
    )
    (net (code "49") (name "Net-(U2-KEY{slash}GSET)") (class "Default")
      (node (ref "R6") (pin "2") (pinfunction "2_2") (pintype "passive"))
      (node (ref "S1") (pin "2") (pinfunction "2_2") (pintype "passive"))
      (node (ref "U2") (pin "20") (pinfunction "KEY/GSET_20") (pintype "passive"))
    )
    (net (code "50") (name "unconnected-(CONN1-L0N-Pad3)") (class "Default")
      (node (ref "CONN1") (pin "3") (pinfunction "L0N_3") (pintype "passive"))
    )
    (net (code "51") (name "unconnected-(CONN1-L0P-Pad2)") (class "Default")
      (node (ref "CONN1") (pin "2") (pinfunction "L0P_2") (pintype "passive"))
    )
    (net (code "52") (name "unconnected-(CONN1-L1N-Pad6)") (class "Default")
      (node (ref "CONN1") (pin "6") (pinfunction "L1N_6") (pintype "passive"))
    )
    (net (code "53") (name "unconnected-(CONN5-PadA8)") (class "Default")
      (node (ref "CONN5") (pin "A8") (pinfunction "A8_A8") (pintype "passive"))
    )
    (net (code "54") (name "unconnected-(CONN5-PadB8)") (class "Default")
      (node (ref "CONN5") (pin "B8") (pinfunction "B8_B8") (pintype "passive"))
    )
    (net (code "55") (name "unconnected-(Q1-D1-Pad2)") (class "Default")
      (node (ref "Q1") (pin "2") (pinfunction "D1_2") (pintype "passive"))
    )
    (net (code "56") (name "unconnected-(Q2-D2-Pad5)") (class "Default")
      (node (ref "Q2") (pin "5") (pinfunction "D2_5") (pintype "passive"))
    )
    (net (code "57") (name "unconnected-(Q5-D1-Pad2)") (class "Default")
      (node (ref "Q5") (pin "2") (pinfunction "D1_2") (pintype "passive"))
    )
    (net (code "58") (name "unconnected-(Q6-D1-Pad2)") (class "Default")
      (node (ref "Q6") (pin "2") (pinfunction "D1_2") (pintype "passive"))
    )
    (net (code "59") (name "unconnected-(Q7-D1-Pad2)") (class "Default")
      (node (ref "Q7") (pin "2") (pinfunction "D1_2") (pintype "passive"))
    )
    (net (code "60") (name "unconnected-(Q8-D1-Pad2)") (class "Default")
      (node (ref "Q8") (pin "2") (pinfunction "D1_2") (pintype "passive"))
    )
    (net (code "61") (name "unconnected-(Q9-D1-Pad2)") (class "Default")
      (node (ref "Q9") (pin "2") (pinfunction "D1_2") (pintype "passive"))
    )
    (net (code "62") (name "unconnected-(U1-TD-Pad4)") (class "Default")
      (node (ref "U1") (pin "4") (pinfunction "TD_4") (pintype "passive"))
    )
  )
)
